# DaughterBoard.net
KiCad netlist of a schematic drawn in Altium Designer
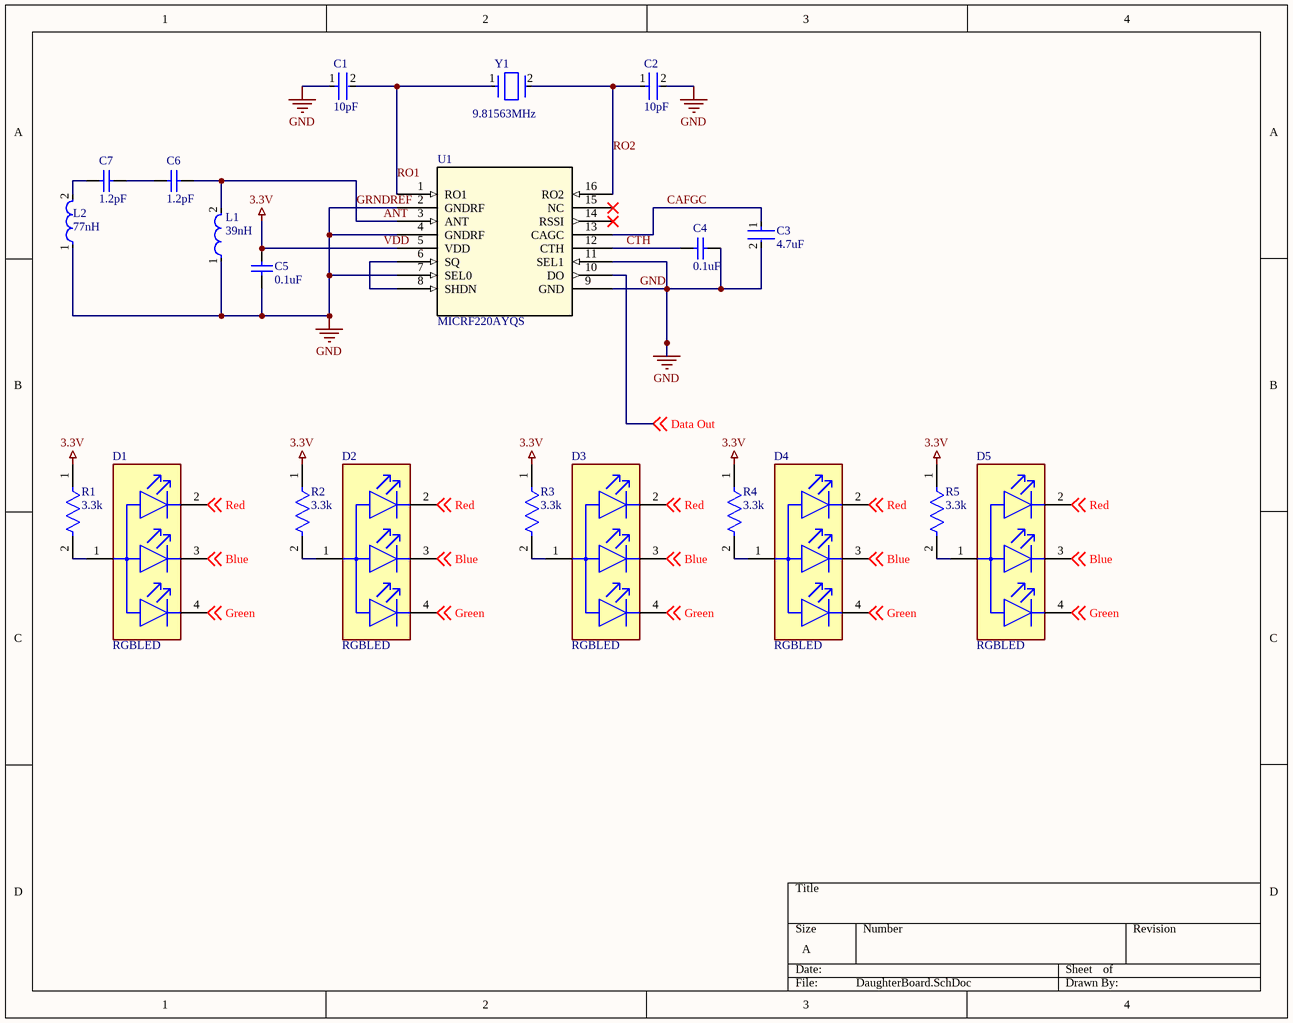
[diagram p0: DaughterBoard.SchDoc]

(export (version "E")
  (design (tool "Eeschema 10.0.6"))
  (components
    (comp (ref "C1")
      (value "10pF")
      (footprint "FP-C0603C-CF-MFG")
      (description "CAP CER 10PF 50V NP0 0603")
      (fields
        (field (name "MANUFACTURER") "KEMET")
        (field (name "MANUFACTURER PART NUMBER") "C0603C100D5GACTU")
      )
      (libsource (lib "Altium Content Vault") (part "b4654b650e69147ec39a6b967a45e02"))
    )
    (comp (ref "C2")
      (value "10pF")
      (footprint "FP-C0603C-CF-MFG")
      (description "CAP CER 10PF 50V NP0 0603")
      (fields
        (field (name "MANUFACTURER") "KEMET")
        (field (name "MANUFACTURER PART NUMBER") "C0603C100D5GACTU")
      )
      (libsource (lib "Altium Content Vault") (part "b4654b650e69147ec39a6b967a45e02"))
    )
    (comp (ref "C3")
      (value "4.7uF")
      (footprint "FP-C1005-050-0_15-IPC_C")
      (description "CAP CER 4.7UF 6.3V X5R 0402")
      (fields (field (name "VOLTAGE") "6.3V") (field (name "TOLERANCE") "20%"))
      (libsource (lib "Altium Content Vault") (part "02cd4be3c70576c341d710602a673aa"))
    )
    (comp (ref "C4")
      (value "0.1uF")
      (footprint "CAPC1005X56X25LL10T15")
      (fields
        (field (name "MANUFACTURER") "AVX Interconnect / Elco")
        (field (name "PART NUMBER") "04026D104KAT2A")
      )
      (libsource (lib "Altium Content Vault") (part "CAP"))
    )
    (comp (ref "C5")
      (value "0.1uF")
      (footprint "CAPC1005X56X25LL10T15")
      (fields
        (field (name "MANUFACTURER") "AVX Interconnect / Elco")
        (field (name "PART NUMBER") "04026D104KAT2A")
      )
      (libsource (lib "Altium Content Vault") (part "CAP"))
    )
    (comp (ref "C6")
      (value "1.2pF")
      (footprint "CAPC1005X55X25LL05T10")
      (fields (field (name "PART NUMBER") "GRM1555C1H1R2WA01D") (field (name "MANUFACTURER") "Murata"))
      (libsource (lib "Altium Content Vault") (part "CAP"))
    )
    (comp (ref "C7")
      (value "1.2pF")
      (footprint "CAPC1005X55X25LL05T10")
      (fields (field (name "PART NUMBER") "GRM1555C1H1R2WA01D") (field (name "MANUFACTURER") "Murata"))
      (libsource (lib "Altium Content Vault") (part "CAP"))
    )
    (comp (ref "D1")
      (value "RGBLED")
      (footprint "FP-SML-LX0404SIUPGUSB-MFG")
      (description "LED RGB CLEAR SMD")
      (libsource (lib "Altium Content Vault") (part "2e8871f6955a40d35a6a753e53ead77"))
    )
    (comp (ref "D2")
      (value "RGBLED")
      (footprint "FP-SML-LX0404SIUPGUSB-MFG")
      (description "LED RGB CLEAR SMD")
      (libsource (lib "Altium Content Vault") (part "2e8871f6955a40d35a6a753e53ead77"))
    )
    (comp (ref "D3")
      (value "RGBLED")
      (footprint "FP-SML-LX0404SIUPGUSB-MFG")
      (description "LED RGB CLEAR SMD")
      (libsource (lib "Altium Content Vault") (part "2e8871f6955a40d35a6a753e53ead77"))
    )
    (comp (ref "D4")
      (value "RGBLED")
      (footprint "FP-SML-LX0404SIUPGUSB-MFG")
      (description "LED RGB CLEAR SMD")
      (libsource (lib "Altium Content Vault") (part "2e8871f6955a40d35a6a753e53ead77"))
    )
    (comp (ref "D5")
      (value "RGBLED")
      (footprint "FP-SML-LX0404SIUPGUSB-MFG")
      (description "LED RGB CLEAR SMD")
      (libsource (lib "Altium Content Vault") (part "2e8871f6955a40d35a6a753e53ead77"))
    )
    (comp (ref "L1")
      (value "39nH")
      (footprint "FP-LQW15AN_80-MFG")
      (description "Wire Wound RF Inductor 39nH ±5% 530mA 0.456Ω 0402 (1005)")
      (fields (field (name "TOLERANCE") "5%"))
      (libsource (lib "Altium Content Vault") (part "725321dda6339637d4d059423bc1c3c"))
    )
    (comp (ref "L2")
      (value "77nH")
      (footprint "FP-LQW15CN_10-MFG")
      (description "Wire Wound Ferrite RF Inductor For Automotive 77nH ±5% 1100mA 0.09Ω 0402 (1005)")
      (fields (field (name "TOLERANCE") "5%"))
      (libsource (lib "Altium Content Vault") (part "725321dda6339637d4d059423bc1c3c"))
    )
    (comp (ref "R1")
      (value "3.3k")
      (footprint "FP-CRCW0603-e3-IPC_A")
      (description "RES Thick Film, 3.3kΩ, 1%, 0.1W, 100ppm/°C, 0603")
      (fields (field (name "TOLERANCE") "1%"))
      (libsource (lib "Altium Content Vault") (part "1029c3af85768c4190bb7ad29bc67b5"))
    )
    (comp (ref "R2")
      (value "3.3k")
      (footprint "FP-CRCW0603-e3-IPC_A")
      (description "RES Thick Film, 3.3kΩ, 1%, 0.1W, 100ppm/°C, 0603")
      (fields (field (name "TOLERANCE") "1%"))
      (libsource (lib "Altium Content Vault") (part "1029c3af85768c4190bb7ad29bc67b5"))
    )
    (comp (ref "R3")
      (value "3.3k")
      (footprint "FP-CRCW0603-e3-IPC_A")
      (description "RES Thick Film, 3.3kΩ, 1%, 0.1W, 100ppm/°C, 0603")
      (fields (field (name "TOLERANCE") "1%"))
      (libsource (lib "Altium Content Vault") (part "1029c3af85768c4190bb7ad29bc67b5"))
    )
    (comp (ref "R4")
      (value "3.3k")
      (footprint "FP-CRCW0603-e3-IPC_A")
      (description "RES Thick Film, 3.3kΩ, 1%, 0.1W, 100ppm/°C, 0603")
      (fields (field (name "TOLERANCE") "1%"))
      (libsource (lib "Altium Content Vault") (part "1029c3af85768c4190bb7ad29bc67b5"))
    )
    (comp (ref "R5")
      (value "3.3k")
      (footprint "FP-CRCW0603-e3-IPC_A")
      (description "RES Thick Film, 3.3kΩ, 1%, 0.1W, 100ppm/°C, 0603")
      (fields (field (name "TOLERANCE") "1%"))
      (libsource (lib "Altium Content Vault") (part "1029c3af85768c4190bb7ad29bc67b5"))
    )
    (comp (ref "U1")
      (value "MICRF220AYQS")
      (footprint "SOP63P600X175-16N")
      (description "No Description Available")
      (fields (field (name "COPYRIGHT") "Copyright (C) 2022 Ultra Librarian. All rights reserved."))
      (libsource (lib "MICRF220AYQS") (part "MICRF220AYQS"))
    )
    (comp (ref "Y1")
      (value "9.81563MHz")
      (footprint "FP-ABM7-MFG")
      (description "Crystal 9.81563MHz ±30ppm 10pF SMD-2 6mm x 3.5mm")
      (libsource (lib "Altium Content Vault") (part "c23a69dc6c9e2f18f2079038eb95dd1"))
    )
  )
  (nets
    (net (code "1") (name "/CAFGC") (class "Default")
      (node (ref "C3") (pin "1") (pinfunction "1_1") (pintype "passive"))
      (node (ref "U1") (pin "13") (pinfunction "CAGC_13") (pintype "passive"))
    )
    (net (code "2") (name "/CTH") (class "Default")
      (node (ref "C4") (pin "1") (pinfunction "1_1") (pintype "passive"))
      (node (ref "U1") (pin "12") (pinfunction "CTH_12") (pintype "passive"))
    )
    (net (code "3") (name "/RO1") (class "Default")
      (node (ref "C1") (pin "2") (pinfunction "2_2") (pintype "passive"))
      (node (ref "U1") (pin "1") (pinfunction "RO1_1") (pintype "input"))
      (node (ref "Y1") (pin "1") (pinfunction "1_1") (pintype "passive"))
    )
    (net (code "4") (name "/RO2") (class "Default")
      (node (ref "C2") (pin "1") (pinfunction "1_1") (pintype "passive"))
      (node (ref "U1") (pin "16") (pinfunction "RO2_16") (pintype "input"))
      (node (ref "Y1") (pin "2") (pinfunction "2_2") (pintype "passive"))
    )
    (net (code "5") (name "3.3V") (class "Default")
      (node (ref "C5") (pin "1") (pinfunction "1_1") (pintype "passive"))
      (node (ref "R1") (pin "1") (pinfunction "1_1") (pintype "passive"))
      (node (ref "R2") (pin "1") (pinfunction "1_1") (pintype "passive"))
      (node (ref "R3") (pin "1") (pinfunction "1_1") (pintype "passive"))
      (node (ref "R4") (pin "1") (pinfunction "1_1") (pintype "passive"))
      (node (ref "R5") (pin "1") (pinfunction "1_1") (pintype "passive"))
      (node (ref "U1") (pin "5") (pinfunction "VDD_5") (pintype "power_in"))
    )
    (net (code "6") (name "Blue") (class "Default")
      (node (ref "D1") (pin "3") (pinfunction "Blue_C_3") (pintype "passive"))
      (node (ref "D2") (pin "3") (pinfunction "Blue_C_3") (pintype "passive"))
      (node (ref "D3") (pin "3") (pinfunction "Blue_C_3") (pintype "passive"))
      (node (ref "D4") (pin "3") (pinfunction "Blue_C_3") (pintype "passive"))
      (node (ref "D5") (pin "3") (pinfunction "Blue_C_3") (pintype "passive"))
    )
    (net (code "7") (name "Data Out") (class "Default")
      (node (ref "U1") (pin "10") (pinfunction "DO_10") (pintype "output"))
    )
    (net (code "8") (name "GND") (class "Default")
      (node (ref "C1") (pin "1") (pinfunction "1_1") (pintype "passive"))
      (node (ref "C2") (pin "2") (pinfunction "2_2") (pintype "passive"))
      (node (ref "C3") (pin "2") (pinfunction "2_2") (pintype "passive"))
      (node (ref "C4") (pin "2") (pinfunction "2_2") (pintype "passive"))
      (node (ref "C5") (pin "2") (pinfunction "2_2") (pintype "passive"))
      (node (ref "C6") (pin "2") (pinfunction "2_2") (pintype "passive"))
      (node (ref "L1") (pin "1") (pinfunction "1_1") (pintype "passive"))
      (node (ref "L1") (pin "2") (pinfunction "2_2") (pintype "passive"))
      (node (ref "L2") (pin "1") (pinfunction "1_1") (pintype "passive"))
      (node (ref "U1") (pin "11") (pinfunction "SEL1_11") (pintype "input"))
      (node (ref "U1") (pin "2") (pinfunction "GNDRF_2") (pintype "power_in"))
      (node (ref "U1") (pin "3") (pinfunction "ANT_3") (pintype "input"))
      (node (ref "U1") (pin "4") (pinfunction "GNDRF_4") (pintype "power_in"))
      (node (ref "U1") (pin "7") (pinfunction "SEL0_7") (pintype "input"))
      (node (ref "U1") (pin "9") (pinfunction "GND_9") (pintype "power_in"))
    )
    (net (code "9") (name "Green") (class "Default")
      (node (ref "D1") (pin "4") (pinfunction "Green_C_4") (pintype "passive"))
      (node (ref "D2") (pin "4") (pinfunction "Green_C_4") (pintype "passive"))
      (node (ref "D3") (pin "4") (pinfunction "Green_C_4") (pintype "passive"))
      (node (ref "D4") (pin "4") (pinfunction "Green_C_4") (pintype "passive"))
      (node (ref "D5") (pin "4") (pinfunction "Green_C_4") (pintype "passive"))
    )
    (net (code "10") (name "Net-(C6-Pad1)") (class "Default")
      (node (ref "C6") (pin "1") (pinfunction "1_1") (pintype "passive"))
      (node (ref "C7") (pin "2") (pinfunction "2_2") (pintype "passive"))
    )
    (net (code "11") (name "Net-(C7-Pad1)") (class "Default")
      (node (ref "C7") (pin "1") (pinfunction "1_1") (pintype "passive"))
      (node (ref "L2") (pin "2") (pinfunction "2_2") (pintype "passive"))
    )
    (net (code "12") (name "Net-(D1-Common_Anode)") (class "Default")
      (node (ref "D1") (pin "1") (pinfunction "Common_Anode_1") (pintype "passive"))
      (node (ref "R1") (pin "2") (pinfunction "2_2") (pintype "passive"))
    )
    (net (code "13") (name "Net-(D2-Common_Anode)") (class "Default")
      (node (ref "D2") (pin "1") (pinfunction "Common_Anode_1") (pintype "passive"))
      (node (ref "R2") (pin "2") (pinfunction "2_2") (pintype "passive"))
    )
    (net (code "14") (name "Net-(D3-Common_Anode)") (class "Default")
      (node (ref "D3") (pin "1") (pinfunction "Common_Anode_1") (pintype "passive"))
      (node (ref "R3") (pin "2") (pinfunction "2_2") (pintype "passive"))
    )
    (net (code "15") (name "Net-(D4-Common_Anode)") (class "Default")
      (node (ref "D4") (pin "1") (pinfunction "Common_Anode_1") (pintype "passive"))
      (node (ref "R4") (pin "2") (pinfunction "2_2") (pintype "passive"))
    )
    (net (code "16") (name "Net-(D5-Common_Anode)") (class "Default")
      (node (ref "D5") (pin "1") (pinfunction "Common_Anode_1") (pintype "passive"))
      (node (ref "R5") (pin "2") (pinfunction "2_2") (pintype "passive"))
    )
    (net (code "17") (name "Net-(U1-SHDN)") (class "Default")
      (node (ref "U1") (pin "6") (pinfunction "SQ_6") (pintype "input"))
      (node (ref "U1") (pin "8") (pinfunction "SHDN_8") (pintype "input"))
    )
    (net (code "18") (name "Red") (class "Default")
      (node (ref "D1") (pin "2") (pinfunction "Red_C_2") (pintype "passive"))
      (node (ref "D2") (pin "2") (pinfunction "Red_C_2") (pintype "passive"))
      (node (ref "D3") (pin "2") (pinfunction "Red_C_2") (pintype "passive"))
      (node (ref "D4") (pin "2") (pinfunction "Red_C_2") (pintype "passive"))
      (node (ref "D5") (pin "2") (pinfunction "Red_C_2") (pintype "passive"))
    )
    (net (code "19") (name "unconnected-(U1-NC-Pad15)") (class "Default")
      (node (ref "U1") (pin "15") (pinfunction "NC_15") (pintype "passive+no_connect"))
    )
    (net (code "20") (name "unconnected-(U1-RSSI-Pad14)") (class "Default")
      (node (ref "U1") (pin "14") (pinfunction "RSSI_14") (pintype "output+no_connect"))
    )
  )
)
